# Triggy_0_1.net
KiCad netlist of a schematic drawn in EAGLE
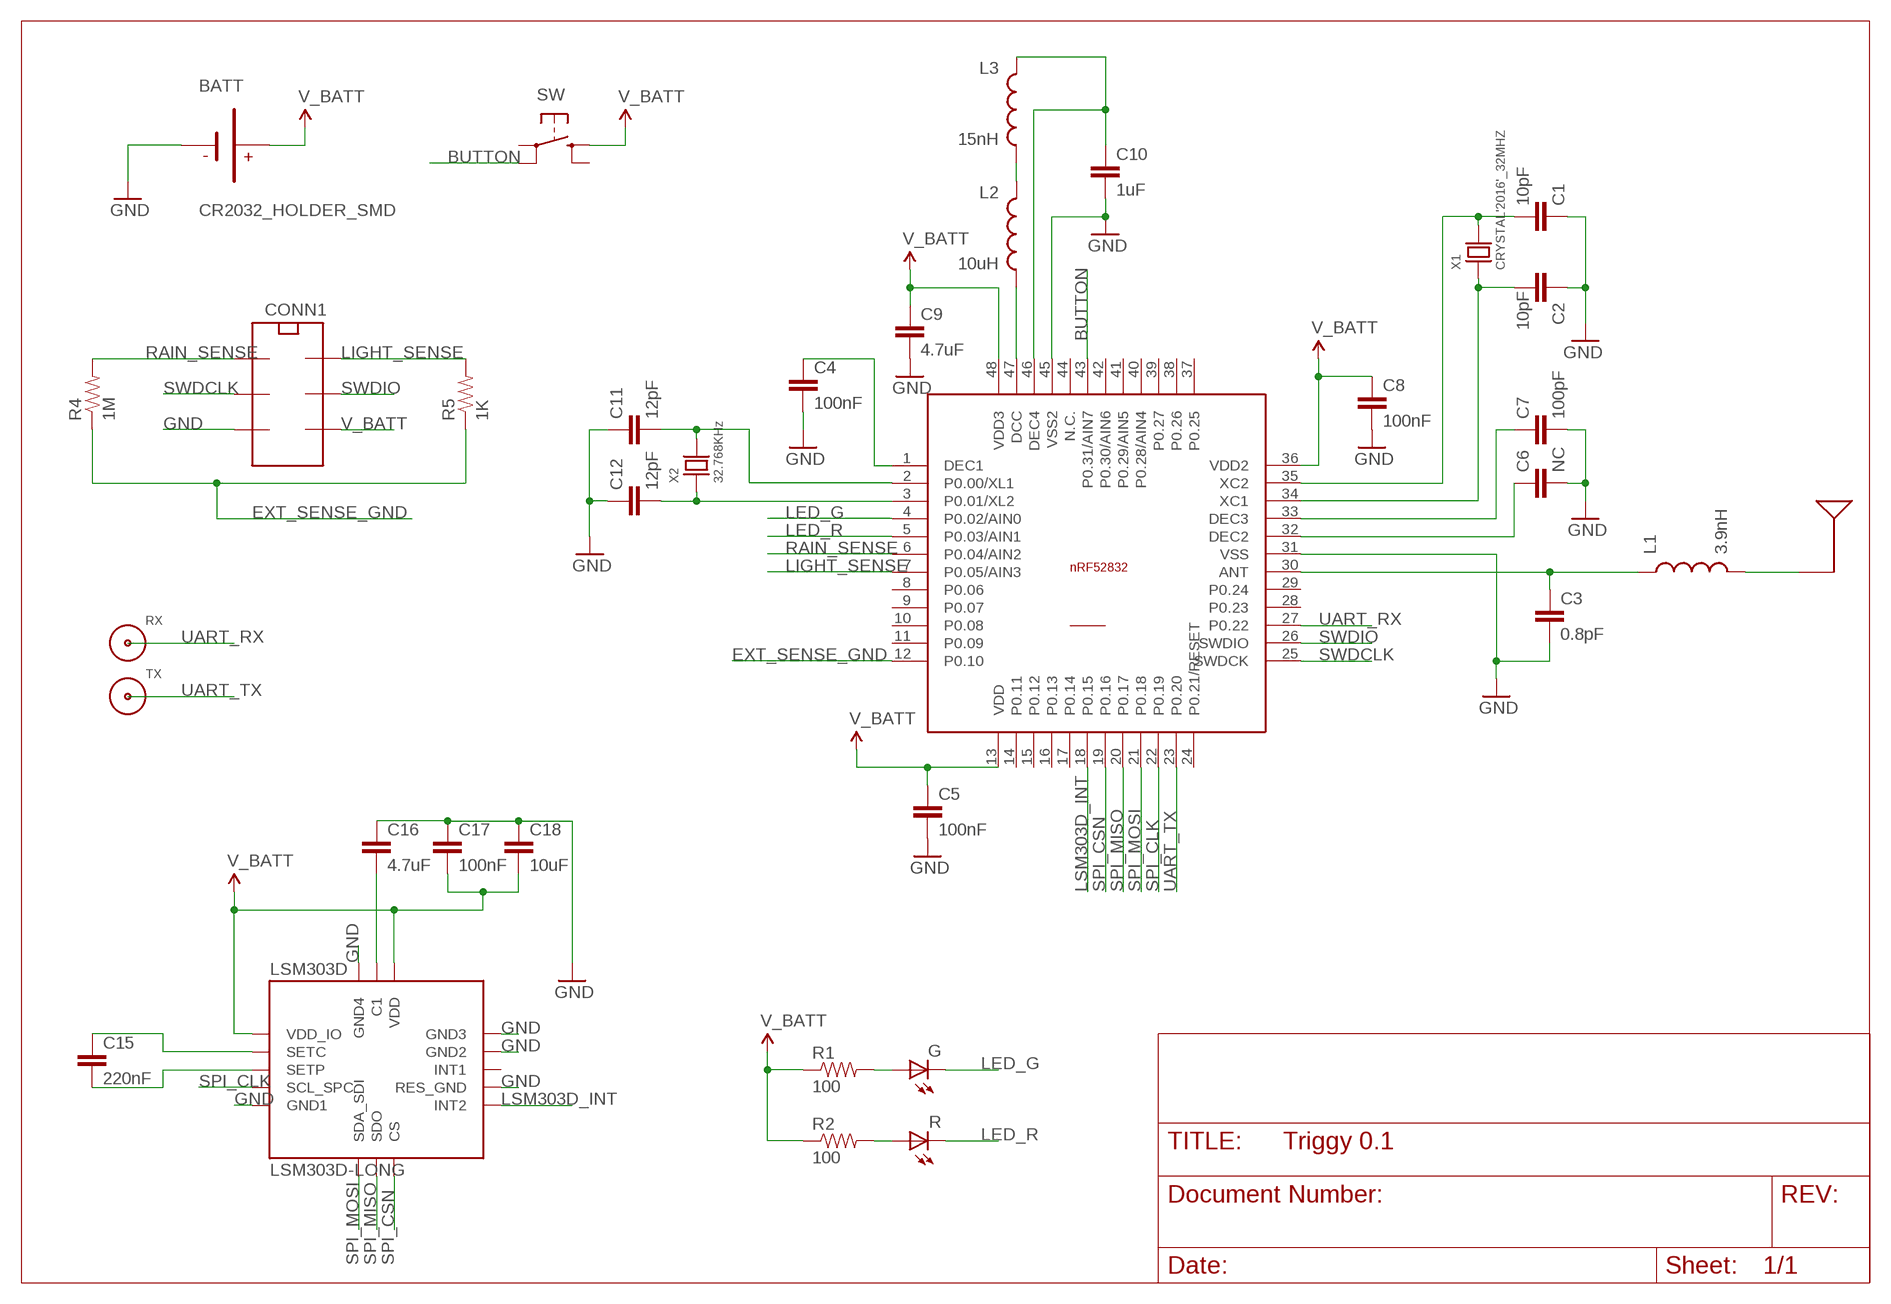
[diagram p0: schematic, sheet 1]

(export (version "E")
  (design (tool "Eeschema 10.0.6"))
  (components
    (comp (ref "ANT")
      (value "ANTENNA_2450AT43A100")
      (footprint "eagle-import:ANTENNA-SMD-7MM")
      (libsource (lib "eagle-import") (part "ANTENNA_2450AT43A100"))
    )
    (comp (ref "BATT")
      (value "CR2032_HOLDER_SMD")
      (footprint "eagle-import:CR2032_HOLDER_SMD")
      (libsource (lib "eagle-import") (part "CR2032_HOLDER_SMD"))
    )
    (comp (ref "C1")
      (value "10pF")
      (footprint "eagle-import:0402-CAP")
      (libsource (lib "eagle-import") (part "CAP0402-CAP"))
    )
    (comp (ref "C2")
      (value "10pF")
      (footprint "eagle-import:0402-CAP")
      (libsource (lib "eagle-import") (part "CAP0402-CAP"))
    )
    (comp (ref "C3")
      (value "0.8pF")
      (footprint "eagle-import:0402-CAP")
      (libsource (lib "eagle-import") (part "CAP0402-CAP"))
    )
    (comp (ref "C4")
      (value "100nF")
      (footprint "eagle-import:0402-CAP")
      (libsource (lib "eagle-import") (part "CAP0402-CAP"))
    )
    (comp (ref "C5")
      (value "100nF")
      (footprint "eagle-import:0402-CAP")
      (libsource (lib "eagle-import") (part "CAP0402-CAP"))
    )
    (comp (ref "C6")
      (value "NC")
      (footprint "eagle-import:0402-CAP")
      (libsource (lib "eagle-import") (part "CAP0402-CAP"))
    )
    (comp (ref "C7")
      (value "100pF")
      (footprint "eagle-import:0402-CAP")
      (libsource (lib "eagle-import") (part "CAP0402-CAP"))
    )
    (comp (ref "C8")
      (value "100nF")
      (footprint "eagle-import:0402-CAP")
      (libsource (lib "eagle-import") (part "CAP0402-CAP"))
    )
    (comp (ref "C9")
      (value "4.7uF")
      (footprint "eagle-import:0603-CAP")
      (libsource (lib "eagle-import") (part "CAP0603-CAP"))
    )
    (comp (ref "C10")
      (value "1uF")
      (footprint "eagle-import:0603-CAP")
      (libsource (lib "eagle-import") (part "CAP0603-CAP"))
    )
    (comp (ref "C11")
      (value "12pF")
      (footprint "eagle-import:0402-CAP")
      (libsource (lib "eagle-import") (part "CAP0402-CAP"))
    )
    (comp (ref "C12")
      (value "12pF")
      (footprint "eagle-import:0402-CAP")
      (libsource (lib "eagle-import") (part "CAP0402-CAP"))
    )
    (comp (ref "C15")
      (value "220nF")
      (footprint "eagle-import:0402-CAP")
      (libsource (lib "eagle-import") (part "CAP0402-CAP"))
    )
    (comp (ref "C16")
      (value "4.7uF")
      (footprint "eagle-import:0603-CAP")
      (libsource (lib "eagle-import") (part "CAP0603-CAP"))
    )
    (comp (ref "C17")
      (value "100nF")
      (footprint "eagle-import:0402-CAP")
      (libsource (lib "eagle-import") (part "CAP0402-CAP"))
    )
    (comp (ref "C18")
      (value "10uF")
      (footprint "eagle-import:0603-CAP")
      (libsource (lib "eagle-import") (part "CAP0603-CAP"))
    )
    (comp (ref "CONN1")
      (value "MOLEX_8734006XX")
      (footprint "eagle-import:MOLEX_8734006XX")
      (libsource (lib "eagle-import") (part "MOLEX_8734006XX"))
    )
    (comp (ref "L1")
      (value "3.9nH")
      (footprint "eagle-import:C0402")
      (libsource (lib "eagle-import") (part "INDUCTOR0402"))
    )
    (comp (ref "L2")
      (value "10uH")
      (footprint "eagle-import:0603")
      (libsource (lib "eagle-import") (part "INDUCTOR0603"))
    )
    (comp (ref "L3")
      (value "15nH")
      (footprint "eagle-import:C0402")
      (libsource (lib "eagle-import") (part "INDUCTOR0402"))
    )
    (comp (ref "LEDS")
      (value "LED-R-G")
      (footprint "eagle-import:LED-RG-SMD-3X2.5MM")
      (libsource (lib "eagle-import") (part "LED-R-G"))
    )
    (comp (ref "LSM303D")
      (value "LSM303D-LONG")
      (footprint "eagle-import:LGA-16-LONG")
      (libsource (lib "eagle-import") (part "LSM303D-LONG"))
    )
    (comp (ref "NRF52832")
      (value "NRF52832_QFN")
      (footprint "eagle-import:QFN48")
      (libsource (lib "eagle-import") (part "NRF52832_QFN"))
    )
    (comp (ref "R1")
      (value "100")
      (footprint "eagle-import:0402-RES")
      (libsource (lib "eagle-import") (part "RESISTOR0402"))
    )
    (comp (ref "R2")
      (value "100")
      (footprint "eagle-import:0402-RES")
      (libsource (lib "eagle-import") (part "RESISTOR0402"))
    )
    (comp (ref "R4")
      (value "1M")
      (footprint "eagle-import:0402-RES")
      (libsource (lib "eagle-import") (part "RESISTOR0402"))
    )
    (comp (ref "R5")
      (value "1K")
      (footprint "eagle-import:0402-RES")
      (libsource (lib "eagle-import") (part "RESISTOR0402"))
    )
    (comp (ref "RX")
      (value "SINGLE_CONN")
      (footprint "eagle-import:SINGLE-CONN")
      (libsource (lib "eagle-import") (part "SINGLE_CONN"))
    )
    (comp (ref "SW")
      (value "SWITCH-PANASONIC")
      (footprint "eagle-import:SWITCH-PANASONIC")
      (libsource (lib "eagle-import") (part "SWITCH-PANASONIC"))
    )
    (comp (ref "TX")
      (value "SINGLE_CONN")
      (footprint "eagle-import:SINGLE-CONN")
      (libsource (lib "eagle-import") (part "SINGLE_CONN"))
    )
    (comp (ref "X1")
      (value "CRYSTAL'2016'_32MHZ")
      (footprint "eagle-import:X4-SMD-2.0X1.6MM")
      (libsource (lib "eagle-import") (part "CRYSTAL'2016'_32MHZ"))
    )
    (comp (ref "X2")
      (value "32.768KHz")
      (footprint "eagle-import:X2-SMD-3.2X1.5MM")
      (libsource (lib "eagle-import") (part "CRYSTAL'3215'"))
    )
  )
  (nets
    (net (code "1") (name "/BUTTON") (class "Default")
      (node (ref "NRF52832") (pin "43") (pinfunction "P0.31/AIN7_43") (pintype "bidirectional"))
      (node (ref "SW") (pin "A'") (pinfunction "2_A'") (pintype "passive"))
    )
    (net (code "2") (name "/EXT_SENSE_GND") (class "Default")
      (node (ref "NRF52832") (pin "12") (pinfunction "P0.10_12") (pintype "bidirectional"))
      (node (ref "R4") (pin "1") (pinfunction "1_1") (pintype "passive"))
      (node (ref "R5") (pin "1") (pinfunction "1_1") (pintype "passive"))
    )
    (net (code "3") (name "/LED_G") (class "Default")
      (node (ref "LEDS") (pin "P$4") (pinfunction "P4_P$4") (pintype "passive"))
      (node (ref "NRF52832") (pin "4") (pinfunction "P0.02/AIN0_4") (pintype "bidirectional"))
    )
    (net (code "4") (name "/LED_R") (class "Default")
      (node (ref "LEDS") (pin "P$2") (pinfunction "P2_P$2") (pintype "passive"))
      (node (ref "NRF52832") (pin "5") (pinfunction "P0.03/AIN1_5") (pintype "bidirectional"))
    )
    (net (code "5") (name "/LIGHT_SENSE") (class "Default")
      (node (ref "CONN1") (pin "P$2") (pinfunction "P$2_P$2") (pintype "bidirectional"))
      (node (ref "NRF52832") (pin "7") (pinfunction "P0.05/AIN3_7") (pintype "bidirectional"))
      (node (ref "R5") (pin "2") (pinfunction "2_2") (pintype "passive"))
    )
    (net (code "6") (name "/LSM303D_INT") (class "Default")
      (node (ref "LSM303D") (pin "9") (pinfunction "INT2_9") (pintype "bidirectional"))
      (node (ref "NRF52832") (pin "18") (pinfunction "P0.15_18") (pintype "bidirectional"))
    )
    (net (code "7") (name "/RAIN_SENSE") (class "Default")
      (node (ref "CONN1") (pin "P$1") (pinfunction "P$1_P$1") (pintype "bidirectional"))
      (node (ref "NRF52832") (pin "6") (pinfunction "P0.04/AIN2_6") (pintype "bidirectional"))
      (node (ref "R4") (pin "2") (pinfunction "2_2") (pintype "passive"))
    )
    (net (code "8") (name "/SPI_CLK") (class "Default")
      (node (ref "LSM303D") (pin "4") (pinfunction "SCL_SPC_4") (pintype "bidirectional"))
      (node (ref "NRF52832") (pin "22") (pinfunction "P0.19_22") (pintype "bidirectional"))
    )
    (net (code "9") (name "/SPI_CSN") (class "Default")
      (node (ref "LSM303D") (pin "8") (pinfunction "CS_8") (pintype "bidirectional"))
      (node (ref "NRF52832") (pin "19") (pinfunction "P0.16_19") (pintype "bidirectional"))
    )
    (net (code "10") (name "/SPI_MISO") (class "Default")
      (node (ref "LSM303D") (pin "7") (pinfunction "SDO_7") (pintype "bidirectional"))
      (node (ref "NRF52832") (pin "20") (pinfunction "P0.17_20") (pintype "bidirectional"))
    )
    (net (code "11") (name "/SPI_MOSI") (class "Default")
      (node (ref "LSM303D") (pin "6") (pinfunction "SDA_SDI_6") (pintype "bidirectional"))
      (node (ref "NRF52832") (pin "21") (pinfunction "P0.18_21") (pintype "bidirectional"))
    )
    (net (code "12") (name "/SWDCLK") (class "Default")
      (node (ref "CONN1") (pin "P$3") (pinfunction "P$3_P$3") (pintype "bidirectional"))
      (node (ref "NRF52832") (pin "25") (pinfunction "SWDCK_25") (pintype "open_collector"))
    )
    (net (code "13") (name "/SWDIO") (class "Default")
      (node (ref "CONN1") (pin "P$4") (pinfunction "P$4_P$4") (pintype "bidirectional"))
      (node (ref "NRF52832") (pin "26") (pinfunction "SWDIO_26") (pintype "bidirectional"))
    )
    (net (code "14") (name "/UART_RX") (class "Default")
      (node (ref "NRF52832") (pin "27") (pinfunction "P0.22_27") (pintype "bidirectional"))
      (node (ref "RX") (pin "1") (pinfunction "1_1") (pintype "bidirectional"))
    )
    (net (code "15") (name "/UART_TX") (class "Default")
      (node (ref "NRF52832") (pin "23") (pinfunction "P0.20_23") (pintype "bidirectional"))
      (node (ref "TX") (pin "1") (pinfunction "1_1") (pintype "bidirectional"))
    )
    (net (code "16") (name "GND") (class "Default")
      (node (ref "BATT") (pin "-") (pinfunction "-_-") (pintype "power_in"))
      (node (ref "C1") (pin "1") (pinfunction "1_1") (pintype "passive"))
      (node (ref "C10") (pin "2") (pinfunction "2_2") (pintype "passive"))
      (node (ref "C11") (pin "1") (pinfunction "1_1") (pintype "passive"))
      (node (ref "C12") (pin "1") (pinfunction "1_1") (pintype "passive"))
      (node (ref "C16") (pin "1") (pinfunction "1_1") (pintype "passive"))
      (node (ref "C17") (pin "1") (pinfunction "1_1") (pintype "passive"))
      (node (ref "C18") (pin "1") (pinfunction "1_1") (pintype "passive"))
      (node (ref "C2") (pin "1") (pinfunction "1_1") (pintype "passive"))
      (node (ref "C3") (pin "2") (pinfunction "2_2") (pintype "passive"))
      (node (ref "C4") (pin "2") (pinfunction "2_2") (pintype "passive"))
      (node (ref "C5") (pin "2") (pinfunction "2_2") (pintype "passive"))
      (node (ref "C6") (pin "2") (pinfunction "2_2") (pintype "passive"))
      (node (ref "C7") (pin "2") (pinfunction "2_2") (pintype "passive"))
      (node (ref "C8") (pin "2") (pinfunction "2_2") (pintype "passive"))
      (node (ref "C9") (pin "2") (pinfunction "2_2") (pintype "passive"))
      (node (ref "CONN1") (pin "P$5") (pinfunction "P$5_P$5") (pintype "bidirectional"))
      (node (ref "LSM303D") (pin "10") (pinfunction "RES_GND_10") (pintype "bidirectional"))
      (node (ref "LSM303D") (pin "12") (pinfunction "GND2_12") (pintype "bidirectional"))
      (node (ref "LSM303D") (pin "13") (pinfunction "GND3_13") (pintype "bidirectional"))
      (node (ref "LSM303D") (pin "16") (pinfunction "GND4_16") (pintype "bidirectional"))
      (node (ref "LSM303D") (pin "5") (pinfunction "GND1_5") (pintype "bidirectional"))
      (node (ref "NRF52832") (pin "31") (pinfunction "VSS_31") (pintype "power_in"))
      (node (ref "NRF52832") (pin "45") (pinfunction "VSS2_45") (pintype "power_in"))
    )
    (net (code "17") (name "Net-(ANT-P$1)") (class "Default")
      (node (ref "ANT") (pin "1") (pinfunction "P$1_1") (pintype "bidirectional"))
      (node (ref "L1") (pin "2") (pinfunction "2_2") (pintype "passive"))
    )
    (net (code "18") (name "Net-(L2-Pad1)") (class "Default")
      (node (ref "L2") (pin "1") (pinfunction "1_1") (pintype "passive"))
      (node (ref "L3") (pin "2") (pinfunction "2_2") (pintype "passive"))
    )
    (net (code "19") (name "Net-(LEDS-P1)") (class "Default")
      (node (ref "LEDS") (pin "P$1") (pinfunction "P1_P$1") (pintype "passive"))
      (node (ref "R2") (pin "2") (pinfunction "2_2") (pintype "passive"))
    )
    (net (code "20") (name "Net-(LEDS-P3)") (class "Default")
      (node (ref "LEDS") (pin "P$3") (pinfunction "P3_P$3") (pintype "passive"))
      (node (ref "R1") (pin "2") (pinfunction "2_2") (pintype "passive"))
    )
    (net (code "21") (name "Net-(LSM303D-C1)") (class "Default")
      (node (ref "C16") (pin "2") (pinfunction "2_2") (pintype "passive"))
      (node (ref "LSM303D") (pin "15") (pinfunction "C1_15") (pintype "bidirectional"))
    )
    (net (code "22") (name "Net-(LSM303D-SETC)") (class "Default")
      (node (ref "C15") (pin "1") (pinfunction "1_1") (pintype "passive"))
      (node (ref "LSM303D") (pin "2") (pinfunction "SETC_2") (pintype "bidirectional"))
    )
    (net (code "23") (name "Net-(LSM303D-SETP)") (class "Default")
      (node (ref "C15") (pin "2") (pinfunction "2_2") (pintype "passive"))
      (node (ref "LSM303D") (pin "3") (pinfunction "SETP_3") (pintype "bidirectional"))
    )
    (net (code "24") (name "Net-(NRF52832-ANT)") (class "Default")
      (node (ref "C3") (pin "1") (pinfunction "1_1") (pintype "passive"))
      (node (ref "L1") (pin "1") (pinfunction "1_1") (pintype "passive"))
      (node (ref "NRF52832") (pin "30") (pinfunction "ANT_30") (pintype "bidirectional"))
    )
    (net (code "25") (name "Net-(NRF52832-DCC)") (class "Default")
      (node (ref "L2") (pin "2") (pinfunction "2_2") (pintype "passive"))
      (node (ref "NRF52832") (pin "47") (pinfunction "DCC_47") (pintype "power_in"))
    )
    (net (code "26") (name "Net-(NRF52832-DEC1)") (class "Default")
      (node (ref "C4") (pin "1") (pinfunction "1_1") (pintype "passive"))
      (node (ref "NRF52832") (pin "1") (pinfunction "DEC1_1") (pintype "power_in"))
    )
    (net (code "27") (name "Net-(NRF52832-DEC2)") (class "Default")
      (node (ref "C6") (pin "1") (pinfunction "1_1") (pintype "passive"))
      (node (ref "NRF52832") (pin "32") (pinfunction "DEC2_32") (pintype "power_in"))
    )
    (net (code "28") (name "Net-(NRF52832-DEC3)") (class "Default")
      (node (ref "C7") (pin "1") (pinfunction "1_1") (pintype "passive"))
      (node (ref "NRF52832") (pin "33") (pinfunction "DEC3_33") (pintype "power_in"))
    )
    (net (code "29") (name "Net-(NRF52832-DEC4)") (class "Default")
      (node (ref "C10") (pin "1") (pinfunction "1_1") (pintype "passive"))
      (node (ref "L3") (pin "1") (pinfunction "1_1") (pintype "passive"))
      (node (ref "NRF52832") (pin "46") (pinfunction "DEC4_46") (pintype "bidirectional"))
    )
    (net (code "30") (name "Net-(NRF52832-P0.00{slash}XL1)") (class "Default")
      (node (ref "C11") (pin "2") (pinfunction "2_2") (pintype "passive"))
      (node (ref "NRF52832") (pin "2") (pinfunction "P0.00/XL1_2") (pintype "bidirectional"))
      (node (ref "X2") (pin "P$2") (pinfunction "2_P$2") (pintype "passive"))
    )
    (net (code "31") (name "Net-(NRF52832-P0.01{slash}XL2)") (class "Default")
      (node (ref "C12") (pin "2") (pinfunction "2_2") (pintype "passive"))
      (node (ref "NRF52832") (pin "3") (pinfunction "P0.01/XL2_3") (pintype "bidirectional"))
      (node (ref "X2") (pin "P$1") (pinfunction "1_P$1") (pintype "passive"))
    )
    (net (code "32") (name "Net-(NRF52832-XC1)") (class "Default")
      (node (ref "C2") (pin "2") (pinfunction "2_2") (pintype "passive"))
      (node (ref "NRF52832") (pin "34") (pinfunction "XC1_34") (pintype "bidirectional"))
      (node (ref "X1") (pin "2") (pinfunction "1_2") (pintype "passive"))
    )
    (net (code "33") (name "Net-(NRF52832-XC2)") (class "Default")
      (node (ref "C1") (pin "2") (pinfunction "2_2") (pintype "passive"))
      (node (ref "NRF52832") (pin "35") (pinfunction "XC2_35") (pintype "bidirectional"))
      (node (ref "X1") (pin "4") (pinfunction "2_4") (pintype "passive"))
    )
    (net (code "34") (name "V_BATT") (class "Default")
      (node (ref "BATT") (pin "+") (pinfunction "+_+") (pintype "power_in"))
      (node (ref "BATT") (pin "+@") (pinfunction "+_+@") (pintype "power_in"))
      (node (ref "C17") (pin "2") (pinfunction "2_2") (pintype "passive"))
      (node (ref "C18") (pin "2") (pinfunction "2_2") (pintype "passive"))
      (node (ref "C5") (pin "1") (pinfunction "1_1") (pintype "passive"))
      (node (ref "C8") (pin "1") (pinfunction "1_1") (pintype "passive"))
      (node (ref "C9") (pin "1") (pinfunction "1_1") (pintype "passive"))
      (node (ref "CONN1") (pin "P$6") (pinfunction "P$6_P$6") (pintype "bidirectional"))
      (node (ref "LSM303D") (pin "1") (pinfunction "VDD_IO_1") (pintype "bidirectional"))
      (node (ref "LSM303D") (pin "14") (pinfunction "VDD_14") (pintype "bidirectional"))
      (node (ref "NRF52832") (pin "13") (pinfunction "VDD_13") (pintype "power_in"))
      (node (ref "NRF52832") (pin "36") (pinfunction "VDD2_36") (pintype "power_in"))
      (node (ref "NRF52832") (pin "48") (pinfunction "VDD3_48") (pintype "power_in"))
      (node (ref "R1") (pin "1") (pinfunction "1_1") (pintype "passive"))
      (node (ref "R2") (pin "1") (pinfunction "1_1") (pintype "passive"))
      (node (ref "SW") (pin "B") (pinfunction "3_B") (pintype "passive"))
    )
    (net (code "35") (name "unconnected-(LSM303D-INT1-Pad11)") (class "Default")
      (node (ref "LSM303D") (pin "11") (pinfunction "INT1_11") (pintype "bidirectional"))
    )
    (net (code "36") (name "unconnected-(NRF52832-N.C.-Pad44)") (class "Default")
      (node (ref "NRF52832") (pin "44") (pinfunction "N.C._44") (pintype "no_connect"))
    )
    (net (code "37") (name "unconnected-(NRF52832-P0.06-Pad8)") (class "Default")
      (node (ref "NRF52832") (pin "8") (pinfunction "P0.06_8") (pintype "bidirectional"))
    )
    (net (code "38") (name "unconnected-(NRF52832-P0.07-Pad9)") (class "Default")
      (node (ref "NRF52832") (pin "9") (pinfunction "P0.07_9") (pintype "bidirectional"))
    )
    (net (code "39") (name "unconnected-(NRF52832-P0.08-Pad10)") (class "Default")
      (node (ref "NRF52832") (pin "10") (pinfunction "P0.08_10") (pintype "bidirectional"))
    )
    (net (code "40") (name "unconnected-(NRF52832-P0.09-Pad11)") (class "Default")
      (node (ref "NRF52832") (pin "11") (pinfunction "P0.09_11") (pintype "bidirectional"))
    )
    (net (code "41") (name "unconnected-(NRF52832-P0.11-Pad14)") (class "Default")
      (node (ref "NRF52832") (pin "14") (pinfunction "P0.11_14") (pintype "bidirectional"))
    )
    (net (code "42") (name "unconnected-(NRF52832-P0.12-Pad15)") (class "Default")
      (node (ref "NRF52832") (pin "15") (pinfunction "P0.12_15") (pintype "bidirectional"))
    )
    (net (code "43") (name "unconnected-(NRF52832-P0.13-Pad16)") (class "Default")
      (node (ref "NRF52832") (pin "16") (pinfunction "P0.13_16") (pintype "bidirectional"))
    )
    (net (code "44") (name "unconnected-(NRF52832-P0.14-Pad17)") (class "Default")
      (node (ref "NRF52832") (pin "17") (pinfunction "P0.14_17") (pintype "bidirectional"))
    )
    (net (code "45") (name "unconnected-(NRF52832-P0.21{slash}RESET-Pad24)") (class "Default")
      (node (ref "NRF52832") (pin "24") (pinfunction "P0.21/RESET_24") (pintype "bidirectional"))
    )
    (net (code "46") (name "unconnected-(NRF52832-P0.23-Pad28)") (class "Default")
      (node (ref "NRF52832") (pin "28") (pinfunction "P0.23_28") (pintype "bidirectional"))
    )
    (net (code "47") (name "unconnected-(NRF52832-P0.24-Pad29)") (class "Default")
      (node (ref "NRF52832") (pin "29") (pinfunction "P0.24_29") (pintype "bidirectional"))
    )
    (net (code "48") (name "unconnected-(NRF52832-P0.25-Pad37)") (class "Default")
      (node (ref "NRF52832") (pin "37") (pinfunction "P0.25_37") (pintype "bidirectional"))
    )
    (net (code "49") (name "unconnected-(NRF52832-P0.26-Pad38)") (class "Default")
      (node (ref "NRF52832") (pin "38") (pinfunction "P0.26_38") (pintype "bidirectional"))
    )
    (net (code "50") (name "unconnected-(NRF52832-P0.27-Pad39)") (class "Default")
      (node (ref "NRF52832") (pin "39") (pinfunction "P0.27_39") (pintype "bidirectional"))
    )
    (net (code "51") (name "unconnected-(NRF52832-P0.28{slash}AIN4-Pad40)") (class "Default")
      (node (ref "NRF52832") (pin "40") (pinfunction "P0.28/AIN4_40") (pintype "bidirectional"))
    )
    (net (code "52") (name "unconnected-(NRF52832-P0.29{slash}AIN5-Pad41)") (class "Default")
      (node (ref "NRF52832") (pin "41") (pinfunction "P0.29/AIN5_41") (pintype "bidirectional"))
    )
    (net (code "53") (name "unconnected-(NRF52832-P0.30{slash}AIN6-Pad42)") (class "Default")
      (node (ref "NRF52832") (pin "42") (pinfunction "P0.30/AIN6_42") (pintype "bidirectional"))
    )
    (net (code "54") (name "unconnected-(NRF52832-SLUG-PadGND)") (class "Default")
      (node (ref "NRF52832") (pin "GND") (pinfunction "SLUG_GND") (pintype "bidirectional"))
    )
    (net (code "55") (name "unconnected-(SW-1-PadA)") (class "Default")
      (node (ref "SW") (pin "A") (pinfunction "1_A") (pintype "passive"))
    )
    (net (code "56") (name "unconnected-(SW-4-PadB')") (class "Default")
      (node (ref "SW") (pin "B'") (pinfunction "4_B'") (pintype "passive"))
    )
  )
)
